# RGB_LEDs.net
KiCad netlist of a schematic drawn in Altium Designer
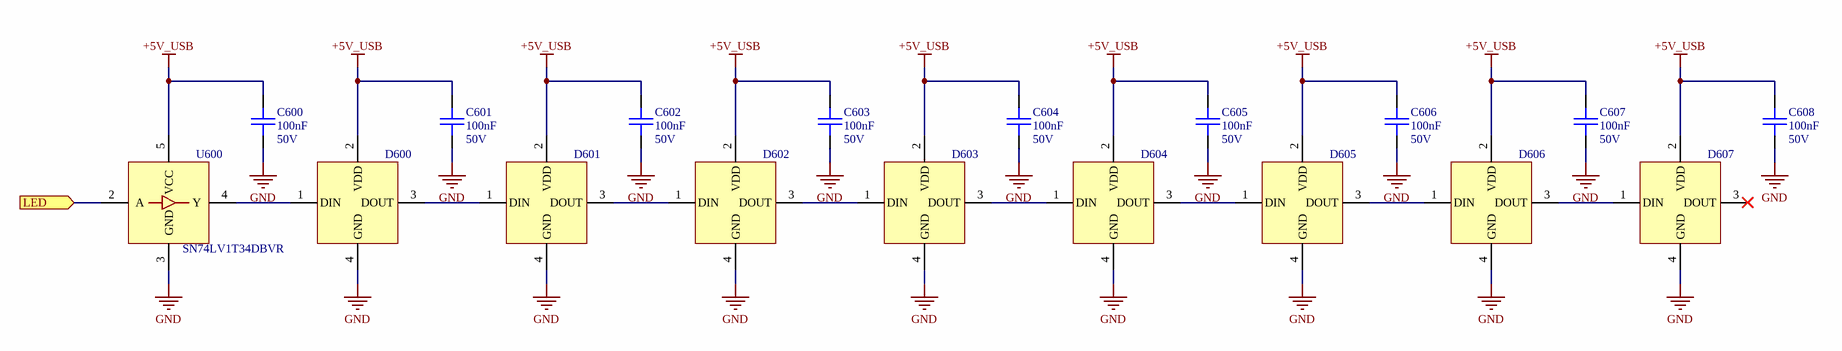
[diagram p0: RGB_LEDs.SchDoc]

(export (version "E")
  (design (tool "Eeschema 10.0.6"))
  (components
    (comp (ref "C600")
      (value "100nF")
      (footprint "C0603")
      (description "General purpose ceramic capacitor")
      (fields
        (field (name "VOLTAGE") "50V")
        (field (name "MANUFACTURER") "TDK Corporation")
        (field (name "MANUFACTURER PART NO") "CGA3E2X7R1H104K080AA")
      )
      (libsource (lib "Moonlight_Library") (part "CAP"))
    )
    (comp (ref "C601")
      (value "100nF")
      (footprint "C0603")
      (description "General purpose ceramic capacitor")
      (fields
        (field (name "VOLTAGE") "50V")
        (field (name "MANUFACTURER") "TDK Corporation")
        (field (name "MANUFACTURER PART NO") "CGA3E2X7R1H104K080AA")
      )
      (libsource (lib "Moonlight_Library") (part "CAP"))
    )
    (comp (ref "C602")
      (value "100nF")
      (footprint "C0603")
      (description "General purpose ceramic capacitor")
      (fields
        (field (name "VOLTAGE") "50V")
        (field (name "MANUFACTURER") "TDK Corporation")
        (field (name "MANUFACTURER PART NO") "CGA3E2X7R1H104K080AA")
      )
      (libsource (lib "Moonlight_Library") (part "CAP"))
    )
    (comp (ref "C603")
      (value "100nF")
      (footprint "C0603")
      (description "General purpose ceramic capacitor")
      (fields
        (field (name "VOLTAGE") "50V")
        (field (name "MANUFACTURER") "TDK Corporation")
        (field (name "MANUFACTURER PART NO") "CGA3E2X7R1H104K080AA")
      )
      (libsource (lib "Moonlight_Library") (part "CAP"))
    )
    (comp (ref "C604")
      (value "100nF")
      (footprint "C0603")
      (description "General purpose ceramic capacitor")
      (fields
        (field (name "VOLTAGE") "50V")
        (field (name "MANUFACTURER") "TDK Corporation")
        (field (name "MANUFACTURER PART NO") "CGA3E2X7R1H104K080AA")
      )
      (libsource (lib "Moonlight_Library") (part "CAP"))
    )
    (comp (ref "C605")
      (value "100nF")
      (footprint "C0603")
      (description "General purpose ceramic capacitor")
      (fields
        (field (name "VOLTAGE") "50V")
        (field (name "MANUFACTURER") "TDK Corporation")
        (field (name "MANUFACTURER PART NO") "CGA3E2X7R1H104K080AA")
      )
      (libsource (lib "Moonlight_Library") (part "CAP"))
    )
    (comp (ref "C606")
      (value "100nF")
      (footprint "C0603")
      (description "General purpose ceramic capacitor")
      (fields
        (field (name "VOLTAGE") "50V")
        (field (name "MANUFACTURER") "TDK Corporation")
        (field (name "MANUFACTURER PART NO") "CGA3E2X7R1H104K080AA")
      )
      (libsource (lib "Moonlight_Library") (part "CAP"))
    )
    (comp (ref "C607")
      (value "100nF")
      (footprint "C0603")
      (description "General purpose ceramic capacitor")
      (fields
        (field (name "VOLTAGE") "50V")
        (field (name "MANUFACTURER") "TDK Corporation")
        (field (name "MANUFACTURER PART NO") "CGA3E2X7R1H104K080AA")
      )
      (libsource (lib "Moonlight_Library") (part "CAP"))
    )
    (comp (ref "C608")
      (value "100nF")
      (footprint "C0603")
      (description "General purpose ceramic capacitor")
      (fields
        (field (name "VOLTAGE") "50V")
        (field (name "MANUFACTURER") "TDK Corporation")
        (field (name "MANUFACTURER PART NO") "CGA3E2X7R1H104K080AA")
      )
      (libsource (lib "Moonlight_Library") (part "CAP"))
    )
    (comp (ref "D600")
      (value "LED_NEOPIXEL")
      (footprint "SK6812B_SIDE")
      (description "Side mounted RGB neopixel")
      (fields (field (name "MANUFACTURER") "Adafruit") (field (name "MANUFACTURER PART NO") "4691"))
      (libsource (lib "Moonlight_Library") (part "LED_NEOPIXEL"))
    )
    (comp (ref "D601")
      (value "LED_NEOPIXEL")
      (footprint "SK6812B_SIDE")
      (description "Side mounted RGB neopixel")
      (fields (field (name "MANUFACTURER") "Adafruit") (field (name "MANUFACTURER PART NO") "4691"))
      (libsource (lib "Moonlight_Library") (part "LED_NEOPIXEL"))
    )
    (comp (ref "D602")
      (value "LED_NEOPIXEL")
      (footprint "SK6812B_SIDE")
      (description "Side mounted RGB neopixel")
      (fields (field (name "MANUFACTURER") "Adafruit") (field (name "MANUFACTURER PART NO") "4691"))
      (libsource (lib "Moonlight_Library") (part "LED_NEOPIXEL"))
    )
    (comp (ref "D603")
      (value "LED_NEOPIXEL")
      (footprint "SK6812B_SIDE")
      (description "Side mounted RGB neopixel")
      (fields (field (name "MANUFACTURER") "Adafruit") (field (name "MANUFACTURER PART NO") "4691"))
      (libsource (lib "Moonlight_Library") (part "LED_NEOPIXEL"))
    )
    (comp (ref "D604")
      (value "LED_NEOPIXEL")
      (footprint "SK6812B_SIDE")
      (description "Side mounted RGB neopixel")
      (fields (field (name "MANUFACTURER") "Adafruit") (field (name "MANUFACTURER PART NO") "4691"))
      (libsource (lib "Moonlight_Library") (part "LED_NEOPIXEL"))
    )
    (comp (ref "D605")
      (value "LED_NEOPIXEL")
      (footprint "SK6812B_SIDE")
      (description "Side mounted RGB neopixel")
      (fields (field (name "MANUFACTURER") "Adafruit") (field (name "MANUFACTURER PART NO") "4691"))
      (libsource (lib "Moonlight_Library") (part "LED_NEOPIXEL"))
    )
    (comp (ref "D606")
      (value "LED_NEOPIXEL")
      (footprint "SK6812B_SIDE")
      (description "Side mounted RGB neopixel")
      (fields (field (name "MANUFACTURER") "Adafruit") (field (name "MANUFACTURER PART NO") "4691"))
      (libsource (lib "Moonlight_Library") (part "LED_NEOPIXEL"))
    )
    (comp (ref "D607")
      (value "LED_NEOPIXEL")
      (footprint "SK6812B_SIDE")
      (description "Side mounted RGB neopixel")
      (fields (field (name "MANUFACTURER") "Adafruit") (field (name "MANUFACTURER PART NO") "4691"))
      (libsource (lib "Moonlight_Library") (part "LED_NEOPIXEL"))
    )
    (comp (ref "U600")
      (value "SN74LV1T34")
      (footprint "SOT-25-5")
      (description "Single Buffer CMOS Level Shifter")
      (fields
        (field (name "MANUFACTURER PART NO") "SN74LV1T34DBVR")
        (field (name "MANUFACTURER") "Texas Instruments")
      )
      (libsource (lib "Moonlight_Library") (part "SN74LV1T34"))
    )
  )
  (nets
    (net (code "1") (name "+5V_USB") (class "Default")
      (node (ref "C600") (pin "1") (pinfunction "1_1") (pintype "passive"))
      (node (ref "C601") (pin "1") (pinfunction "1_1") (pintype "passive"))
      (node (ref "C602") (pin "1") (pinfunction "1_1") (pintype "passive"))
      (node (ref "C603") (pin "1") (pinfunction "1_1") (pintype "passive"))
      (node (ref "C604") (pin "1") (pinfunction "1_1") (pintype "passive"))
      (node (ref "C605") (pin "1") (pinfunction "1_1") (pintype "passive"))
      (node (ref "C606") (pin "1") (pinfunction "1_1") (pintype "passive"))
      (node (ref "C607") (pin "1") (pinfunction "1_1") (pintype "passive"))
      (node (ref "C608") (pin "1") (pinfunction "1_1") (pintype "passive"))
      (node (ref "D600") (pin "2") (pinfunction "VDD_2") (pintype "passive"))
      (node (ref "D601") (pin "2") (pinfunction "VDD_2") (pintype "passive"))
      (node (ref "D602") (pin "2") (pinfunction "VDD_2") (pintype "passive"))
      (node (ref "D603") (pin "2") (pinfunction "VDD_2") (pintype "passive"))
      (node (ref "D604") (pin "2") (pinfunction "VDD_2") (pintype "passive"))
      (node (ref "D605") (pin "2") (pinfunction "VDD_2") (pintype "passive"))
      (node (ref "D606") (pin "2") (pinfunction "VDD_2") (pintype "passive"))
      (node (ref "D607") (pin "2") (pinfunction "VDD_2") (pintype "passive"))
      (node (ref "U600") (pin "5") (pinfunction "VCC_5") (pintype "passive"))
    )
    (net (code "2") (name "/LED") (class "Default")
      (node (ref "U600") (pin "2") (pinfunction "A_2") (pintype "passive"))
    )
    (net (code "3") (name "GND") (class "Default")
      (node (ref "C600") (pin "2") (pinfunction "2_2") (pintype "passive"))
      (node (ref "C601") (pin "2") (pinfunction "2_2") (pintype "passive"))
      (node (ref "C602") (pin "2") (pinfunction "2_2") (pintype "passive"))
      (node (ref "C603") (pin "2") (pinfunction "2_2") (pintype "passive"))
      (node (ref "C604") (pin "2") (pinfunction "2_2") (pintype "passive"))
      (node (ref "C605") (pin "2") (pinfunction "2_2") (pintype "passive"))
      (node (ref "C606") (pin "2") (pinfunction "2_2") (pintype "passive"))
      (node (ref "C607") (pin "2") (pinfunction "2_2") (pintype "passive"))
      (node (ref "C608") (pin "2") (pinfunction "2_2") (pintype "passive"))
      (node (ref "D600") (pin "4") (pinfunction "GND_4") (pintype "passive"))
      (node (ref "D601") (pin "4") (pinfunction "GND_4") (pintype "passive"))
      (node (ref "D602") (pin "4") (pinfunction "GND_4") (pintype "passive"))
      (node (ref "D603") (pin "4") (pinfunction "GND_4") (pintype "passive"))
      (node (ref "D604") (pin "4") (pinfunction "GND_4") (pintype "passive"))
      (node (ref "D605") (pin "4") (pinfunction "GND_4") (pintype "passive"))
      (node (ref "D606") (pin "4") (pinfunction "GND_4") (pintype "passive"))
      (node (ref "D607") (pin "4") (pinfunction "GND_4") (pintype "passive"))
      (node (ref "U600") (pin "3") (pinfunction "GND_3") (pintype "passive"))
    )
    (net (code "4") (name "Net-(D600-DIN)") (class "Default")
      (node (ref "D600") (pin "1") (pinfunction "DIN_1") (pintype "passive"))
      (node (ref "U600") (pin "4") (pinfunction "Y_4") (pintype "passive"))
    )
    (net (code "5") (name "Net-(D600-DOUT)") (class "Default")
      (node (ref "D600") (pin "3") (pinfunction "DOUT_3") (pintype "passive"))
      (node (ref "D601") (pin "1") (pinfunction "DIN_1") (pintype "passive"))
    )
    (net (code "6") (name "Net-(D601-DOUT)") (class "Default")
      (node (ref "D601") (pin "3") (pinfunction "DOUT_3") (pintype "passive"))
      (node (ref "D602") (pin "1") (pinfunction "DIN_1") (pintype "passive"))
    )
    (net (code "7") (name "Net-(D602-DOUT)") (class "Default")
      (node (ref "D602") (pin "3") (pinfunction "DOUT_3") (pintype "passive"))
      (node (ref "D603") (pin "1") (pinfunction "DIN_1") (pintype "passive"))
    )
    (net (code "8") (name "Net-(D603-DOUT)") (class "Default")
      (node (ref "D603") (pin "3") (pinfunction "DOUT_3") (pintype "passive"))
      (node (ref "D604") (pin "1") (pinfunction "DIN_1") (pintype "passive"))
    )
    (net (code "9") (name "Net-(D604-DOUT)") (class "Default")
      (node (ref "D604") (pin "3") (pinfunction "DOUT_3") (pintype "passive"))
      (node (ref "D605") (pin "1") (pinfunction "DIN_1") (pintype "passive"))
    )
    (net (code "10") (name "Net-(D605-DOUT)") (class "Default")
      (node (ref "D605") (pin "3") (pinfunction "DOUT_3") (pintype "passive"))
      (node (ref "D606") (pin "1") (pinfunction "DIN_1") (pintype "passive"))
    )
    (net (code "11") (name "Net-(D606-DOUT)") (class "Default")
      (node (ref "D606") (pin "3") (pinfunction "DOUT_3") (pintype "passive"))
      (node (ref "D607") (pin "1") (pinfunction "DIN_1") (pintype "passive"))
    )
    (net (code "12") (name "unconnected-(D607-DOUT-Pad3)") (class "Default")
      (node (ref "D607") (pin "3") (pinfunction "DOUT_3") (pintype "passive+no_connect"))
    )
  )
)
